# Connectors.net
KiCad netlist of a schematic drawn in Altium Designer
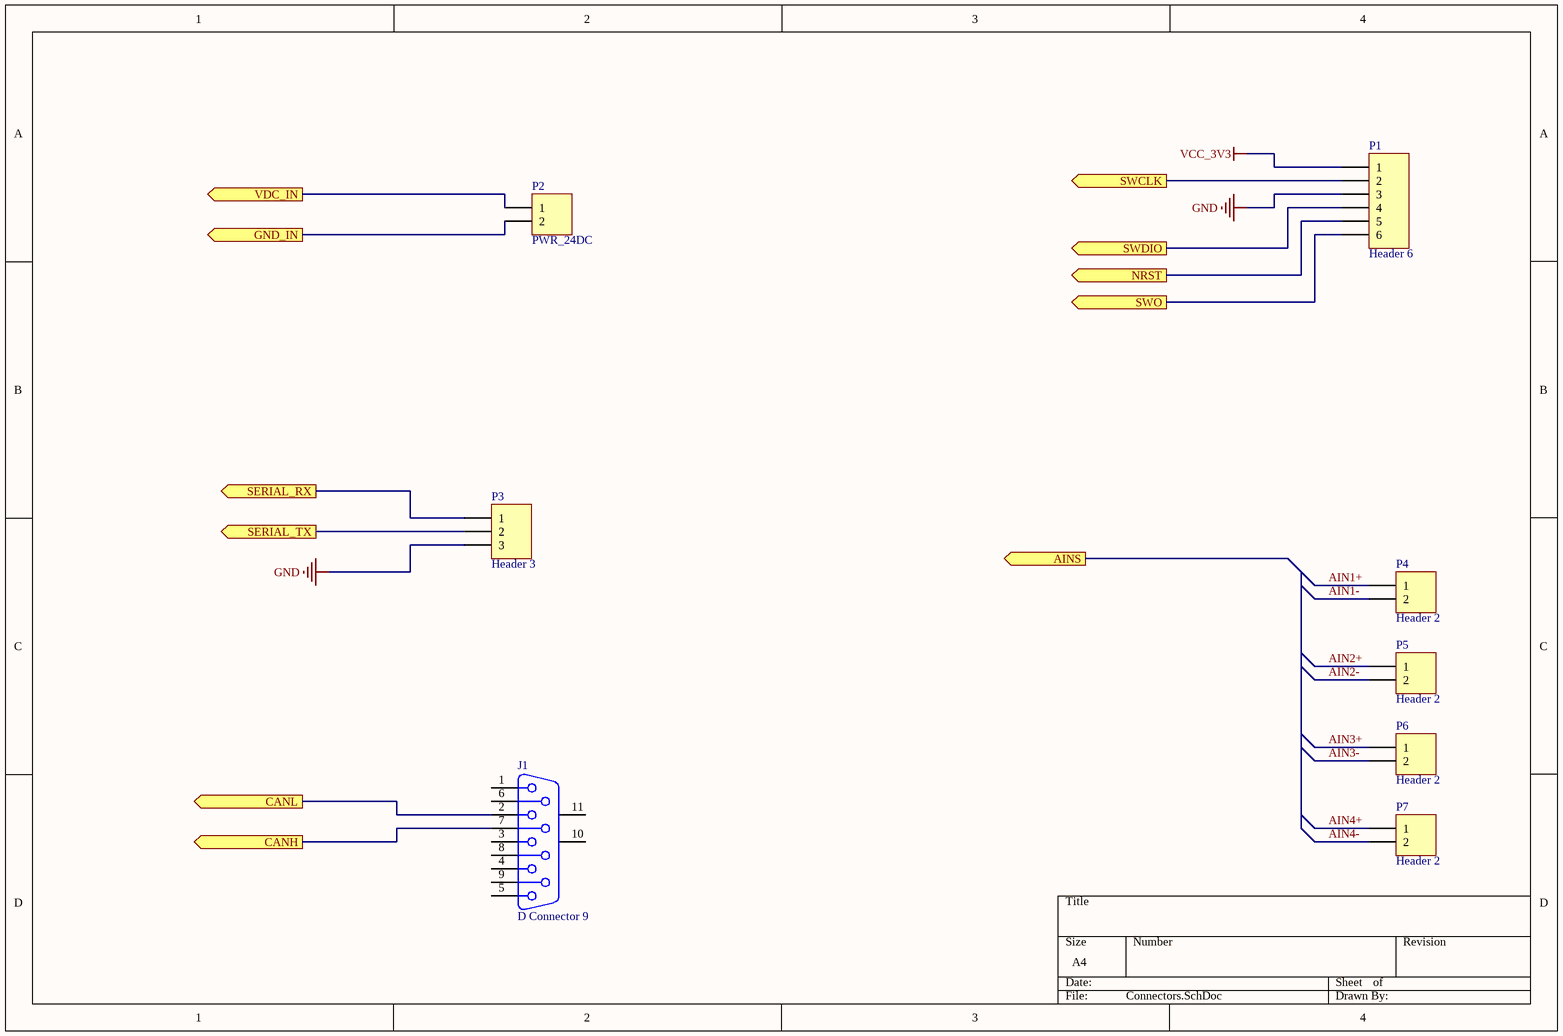
[diagram p0: Connectors.SchDoc]

(export (version "E")
  (design (tool "Eeschema 10.0.6"))
  (components
    (comp (ref "J1")
      (value "D Connector 9")
      (footprint "DSUB1.385-2H9")
      (description "Receptacle Assembly, 9 Position, Right Angle")
      (fields (field (name "PUBLISHER") "Altium Limited"))
      (libsource (lib "Miscellaneous Connectors") (part "D Connector 9"))
    )
    (comp (ref "P1")
      (value "Header 6")
      (footprint "HDR1X6")
      (description "Header, 6-Pin")
      (fields (field (name "PUBLISHER") "Altium Limited"))
      (libsource (lib "Miscellaneous Connectors") (part "Header 6"))
    )
    (comp (ref "P2")
      (value "PWR_24DC")
      (footprint "HDR1X2")
      (description "2-Pin Connector")
      (fields (field (name "PUBLISHER") "Altium Limited"))
      (libsource (lib "Miscellaneous Connectors") (part "Header 2"))
    )
    (comp (ref "P3")
      (value "Header 3")
      (footprint "HDR1X3")
      (description "Header, 3-Pin")
      (fields (field (name "PUBLISHER") "Altium Limited"))
      (libsource (lib "Miscellaneous Connectors") (part "Header 3"))
    )
    (comp (ref "P4")
      (value "Header 2")
      (footprint "HDR1X2")
      (description "Header, 2-Pin")
      (fields (field (name "PUBLISHER") "Altium Limited"))
      (libsource (lib "Miscellaneous Connectors") (part "Header 2"))
    )
    (comp (ref "P5")
      (value "Header 2")
      (footprint "HDR1X2")
      (description "Header, 2-Pin")
      (fields (field (name "PUBLISHER") "Altium Limited"))
      (libsource (lib "Miscellaneous Connectors") (part "Header 2"))
    )
    (comp (ref "P6")
      (value "Header 2")
      (footprint "HDR1X2")
      (description "Header, 2-Pin")
      (fields (field (name "PUBLISHER") "Altium Limited"))
      (libsource (lib "Miscellaneous Connectors") (part "Header 2"))
    )
    (comp (ref "P7")
      (value "Header 2")
      (footprint "HDR1X2")
      (description "Header, 2-Pin")
      (fields (field (name "PUBLISHER") "Altium Limited"))
      (libsource (lib "Miscellaneous Connectors") (part "Header 2"))
    )
  )
  (nets
    (net (code "1") (name "/AIN1+") (class "Default")
      (node (ref "P4") (pin "1") (pinfunction "1_1") (pintype "passive"))
    )
    (net (code "2") (name "/AIN1-") (class "Default")
      (node (ref "P4") (pin "2") (pinfunction "2_2") (pintype "passive"))
    )
    (net (code "3") (name "/AIN2+") (class "Default")
      (node (ref "P5") (pin "1") (pinfunction "1_1") (pintype "passive"))
    )
    (net (code "4") (name "/AIN2-") (class "Default")
      (node (ref "P5") (pin "2") (pinfunction "2_2") (pintype "passive"))
    )
    (net (code "5") (name "/AIN3+") (class "Default")
      (node (ref "P6") (pin "1") (pinfunction "1_1") (pintype "passive"))
    )
    (net (code "6") (name "/AIN3-") (class "Default")
      (node (ref "P6") (pin "2") (pinfunction "2_2") (pintype "passive"))
    )
    (net (code "7") (name "/AIN4+") (class "Default")
      (node (ref "P7") (pin "1") (pinfunction "1_1") (pintype "passive"))
    )
    (net (code "8") (name "/AIN4-") (class "Default")
      (node (ref "P7") (pin "2") (pinfunction "2_2") (pintype "passive"))
    )
    (net (code "10") (name "/CANH") (class "Default")
      (node (ref "J1") (pin "7") (pinfunction "7_7") (pintype "passive"))
    )
    (net (code "11") (name "/CANL") (class "Default")
      (node (ref "J1") (pin "2") (pinfunction "2_2") (pintype "passive"))
    )
    (net (code "12") (name "/GND_IN") (class "Default")
      (node (ref "P2") (pin "2") (pinfunction "2_2") (pintype "passive"))
    )
    (net (code "13") (name "/NRST") (class "Default")
      (node (ref "P1") (pin "5") (pinfunction "5_5") (pintype "passive"))
    )
    (net (code "14") (name "/SERIAL_RX") (class "Default")
      (node (ref "P3") (pin "1") (pinfunction "1_1") (pintype "passive"))
    )
    (net (code "15") (name "/SERIAL_TX") (class "Default")
      (node (ref "P3") (pin "2") (pinfunction "2_2") (pintype "passive"))
    )
    (net (code "16") (name "/SWCLK") (class "Default")
      (node (ref "P1") (pin "2") (pinfunction "2_2") (pintype "passive"))
    )
    (net (code "17") (name "/SWDIO") (class "Default")
      (node (ref "P1") (pin "4") (pinfunction "4_4") (pintype "passive"))
    )
    (net (code "18") (name "/SWO") (class "Default")
      (node (ref "P1") (pin "6") (pinfunction "6_6") (pintype "passive"))
    )
    (net (code "19") (name "/VDC_IN") (class "Default")
      (node (ref "P2") (pin "1") (pinfunction "1_1") (pintype "passive"))
    )
    (net (code "20") (name "GND") (class "Default")
      (node (ref "P1") (pin "3") (pinfunction "3_3") (pintype "passive"))
      (node (ref "P3") (pin "3") (pinfunction "3_3") (pintype "passive"))
    )
    (net (code "21") (name "VCC_3V3") (class "Default")
      (node (ref "P1") (pin "1") (pinfunction "1_1") (pintype "passive"))
    )
    (net (code "22") (name "unconnected-(J1-MH1-Pad10)") (class "Default")
      (node (ref "J1") (pin "10") (pinfunction "MH1_10") (pintype "passive"))
    )
    (net (code "23") (name "unconnected-(J1-MH2-Pad11)") (class "Default")
      (node (ref "J1") (pin "11") (pinfunction "MH2_11") (pintype "passive"))
    )
    (net (code "24") (name "unconnected-(J1-Pad1)") (class "Default")
      (node (ref "J1") (pin "1") (pinfunction "1_1") (pintype "passive"))
    )
    (net (code "25") (name "unconnected-(J1-Pad3)") (class "Default")
      (node (ref "J1") (pin "3") (pinfunction "3_3") (pintype "passive"))
    )
    (net (code "26") (name "unconnected-(J1-Pad4)") (class "Default")
      (node (ref "J1") (pin "4") (pinfunction "4_4") (pintype "passive"))
    )
    (net (code "27") (name "unconnected-(J1-Pad5)") (class "Default")
      (node (ref "J1") (pin "5") (pinfunction "5_5") (pintype "passive"))
    )
    (net (code "28") (name "unconnected-(J1-Pad6)") (class "Default")
      (node (ref "J1") (pin "6") (pinfunction "6_6") (pintype "passive"))
    )
    (net (code "29") (name "unconnected-(J1-Pad8)") (class "Default")
      (node (ref "J1") (pin "8") (pinfunction "8_8") (pintype "passive"))
    )
    (net (code "30") (name "unconnected-(J1-Pad9)") (class "Default")
      (node (ref "J1") (pin "9") (pinfunction "9_9") (pintype "passive"))
    )
  )
)
